# Adafruit_Pro_Trinket_3v3_modified.net
KiCad netlist of a schematic drawn in EAGLE
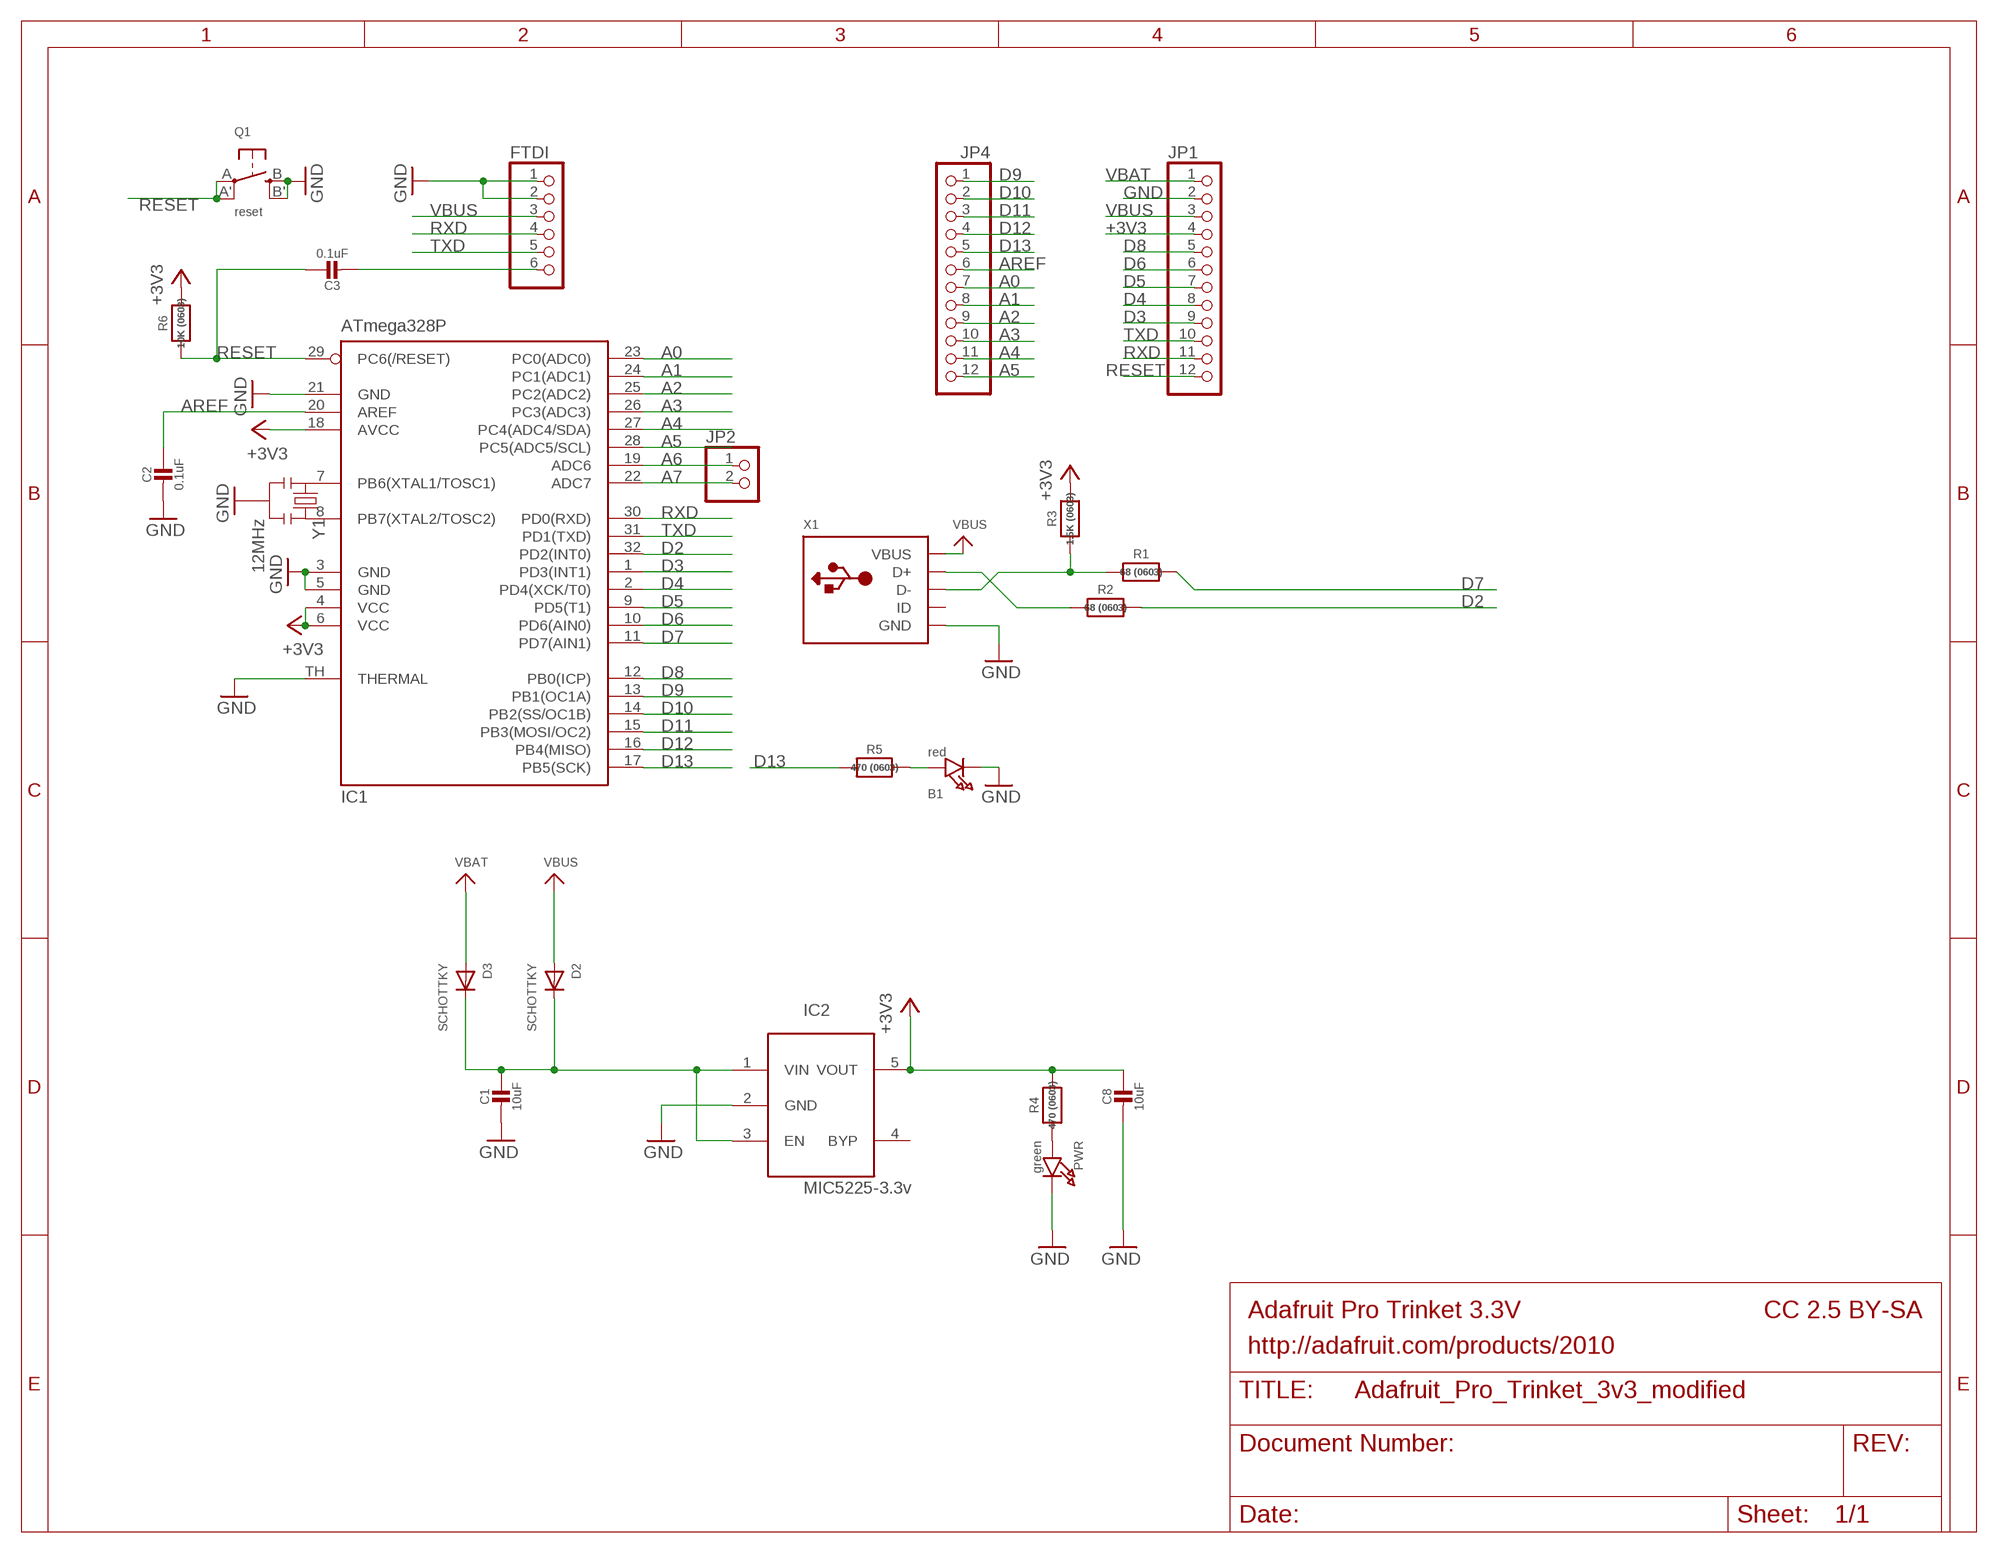
[diagram p0: schematic, sheet 1]

(export (version "E")
  (design (tool "Eeschema 10.0.6"))
  (components
    (comp (ref "B1")
      (value "red")
      (footprint "eagle-import:CHIPLED_0805_NOOUTLINE")
      (libsource (lib "eagle-import") (part "LED0805_NOOUTLINE"))
    )
    (comp (ref "C1")
      (value "10uF")
      (footprint "eagle-import:0805-NO")
      (libsource (lib "eagle-import") (part "CAP_CERAMIC0805-NOOUTLINE"))
    )
    (comp (ref "C2")
      (value "0.1uF")
      (footprint "eagle-import:_0805MP")
      (libsource (lib "eagle-import") (part "CAP_CERAMIC_0805MP"))
    )
    (comp (ref "C3")
      (value "0.1uF")
      (footprint "eagle-import:0805-NO")
      (libsource (lib "eagle-import") (part "CAP_CERAMIC0805-NOOUTLINE"))
    )
    (comp (ref "C8")
      (value "10uF")
      (footprint "eagle-import:0805-NO")
      (libsource (lib "eagle-import") (part "CAP_CERAMIC0805-NOOUTLINE"))
    )
    (comp (ref "D2")
      (value "SCHOTTKY")
      (footprint "eagle-import:ADAFRUIT_SOD-123FL")
      (libsource (lib "eagle-import") (part "ADAFRUIT_DIODE_SOD-123FL"))
    )
    (comp (ref "D3")
      (value "SCHOTTKY")
      (footprint "eagle-import:ADAFRUIT_SOD-123FL")
      (libsource (lib "eagle-import") (part "ADAFRUIT_DIODE_SOD-123FL"))
    )
    (comp (ref "FTDI")
      (value "PINHD-1X6CB")
      (footprint "eagle-import:1X06-CLEANBIG")
      (libsource (lib "eagle-import") (part "PINHD-1X6CB"))
    )
    (comp (ref "IC1")
      (value "ATmega328P")
      (footprint "eagle-import:MLF32-TH")
      (fields (field (name "MPN") "ATMEGA88PA-MU"))
      (libsource (lib "eagle-import") (part "MEGA8-MI"))
    )
    (comp (ref "IC2")
      (value "MIC5225-3.3v")
      (footprint "eagle-import:SOT23-5L")
      (libsource (lib "eagle-import") (part "LP298XS"))
    )
    (comp (ref "JP1")
      (value "PINHD-1X12-CB")
      (footprint "eagle-import:1X12-CB")
      (libsource (lib "eagle-import") (part "PINHD-1X12-CB"))
    )
    (comp (ref "JP2")
      (value "HEADER-1X2ROUND")
      (footprint "eagle-import:1X02_ROUND")
      (libsource (lib "eagle-import") (part "HEADER-1X2ROUND"))
    )
    (comp (ref "JP4")
      (value "PINHD-1X12-CB")
      (footprint "eagle-import:1X12-CB")
      (libsource (lib "eagle-import") (part "PINHD-1X12-CB"))
    )
    (comp (ref "PWR")
      (value "green")
      (footprint "eagle-import:CHIPLED_0805_NOOUTLINE")
      (libsource (lib "eagle-import") (part "LED0805_NOOUTLINE"))
    )
    (comp (ref "Q1")
      (value "reset")
      (footprint "eagle-import:BTN_KMR2_4.6X2.8")
      (libsource (lib "eagle-import") (part "SWITCH_TACT_SMT4.6X2.8"))
    )
    (comp (ref "R1")
      (value "68 (0603)")
      (footprint "eagle-import:0603-NO")
      (libsource (lib "eagle-import") (part "RESISTOR_0603_NOOUT"))
    )
    (comp (ref "R2")
      (value "68 (0603)")
      (footprint "eagle-import:0603-NO")
      (libsource (lib "eagle-import") (part "RESISTOR_0603_NOOUT"))
    )
    (comp (ref "R3")
      (value "1.5K (0603)")
      (footprint "eagle-import:0603-NO")
      (libsource (lib "eagle-import") (part "RESISTOR_0603_NOOUT"))
    )
    (comp (ref "R4")
      (value "470 (0603)")
      (footprint "eagle-import:0603-NO")
      (libsource (lib "eagle-import") (part "RESISTOR_0603_NOOUT"))
    )
    (comp (ref "R5")
      (value "470 (0603)")
      (footprint "eagle-import:0603-NO")
      (libsource (lib "eagle-import") (part "RESISTOR_0603_NOOUT"))
    )
    (comp (ref "R6")
      (value "10K (0603)")
      (footprint "eagle-import:0805-NO")
      (libsource (lib "eagle-import") (part "RESISTOR0805_NOOUTLINE"))
    )
    (comp (ref "X1")
      (value "MICROBUILDER_USBMICRO_20329")
      (footprint "eagle-import:MICROBUILDER_4UCONN_20329")
      (libsource (lib "eagle-import") (part "MICROBUILDER_USBMICRO_20329"))
    )
    (comp (ref "Y1")
      (value "12MHz")
      (footprint "eagle-import:RESONATOR-SMD")
      (libsource (lib "eagle-import") (part "RESONATORSMD"))
    )
  )
  (nets
    (net (code "1") (name "+3V3") (class "Default")
      (node (ref "C8") (pin "1") (pinfunction "1_1") (pintype "passive"))
      (node (ref "IC1") (pin "18") (pinfunction "AVCC_18") (pintype "power_in"))
      (node (ref "IC1") (pin "4") (pinfunction "VCC_4") (pintype "power_in"))
      (node (ref "IC1") (pin "6") (pinfunction "VCC_6") (pintype "power_in"))
      (node (ref "IC2") (pin "5") (pinfunction "VOUT_5") (pintype "bidirectional"))
      (node (ref "JP1") (pin "4") (pinfunction "4_4") (pintype "passive"))
      (node (ref "R3") (pin "2") (pinfunction "2_2") (pintype "passive"))
      (node (ref "R4") (pin "2") (pinfunction "2_2") (pintype "passive"))
      (node (ref "R6") (pin "2") (pinfunction "2_2") (pintype "passive"))
    )
    (net (code "2") (name "/A0") (class "Default")
      (node (ref "IC1") (pin "23") (pinfunction "PC0(ADC0)_23") (pintype "bidirectional"))
      (node (ref "JP4") (pin "7") (pinfunction "7_7") (pintype "passive"))
    )
    (net (code "3") (name "/A1") (class "Default")
      (node (ref "IC1") (pin "24") (pinfunction "PC1(ADC1)_24") (pintype "bidirectional"))
      (node (ref "JP4") (pin "8") (pinfunction "8_8") (pintype "passive"))
    )
    (net (code "4") (name "/A2") (class "Default")
      (node (ref "IC1") (pin "25") (pinfunction "PC2(ADC2)_25") (pintype "bidirectional"))
      (node (ref "JP4") (pin "9") (pinfunction "9_9") (pintype "passive"))
    )
    (net (code "5") (name "/A3") (class "Default")
      (node (ref "IC1") (pin "26") (pinfunction "PC3(ADC3)_26") (pintype "bidirectional"))
      (node (ref "JP4") (pin "10") (pinfunction "10_10") (pintype "passive"))
    )
    (net (code "6") (name "/A4") (class "Default")
      (node (ref "IC1") (pin "27") (pinfunction "PC4(ADC4/SDA)_27") (pintype "bidirectional"))
      (node (ref "JP4") (pin "11") (pinfunction "11_11") (pintype "passive"))
    )
    (net (code "7") (name "/A5") (class "Default")
      (node (ref "IC1") (pin "28") (pinfunction "PC5(ADC5/SCL)_28") (pintype "bidirectional"))
      (node (ref "JP4") (pin "12") (pinfunction "12_12") (pintype "passive"))
    )
    (net (code "8") (name "/A6") (class "Default")
      (node (ref "IC1") (pin "19") (pinfunction "ADC6_19") (pintype "bidirectional"))
      (node (ref "JP2") (pin "1") (pinfunction "1_1") (pintype "passive"))
    )
    (net (code "9") (name "/A7") (class "Default")
      (node (ref "IC1") (pin "22") (pinfunction "ADC7_22") (pintype "bidirectional"))
      (node (ref "JP2") (pin "2") (pinfunction "2_2") (pintype "passive"))
    )
    (net (code "10") (name "/AREF") (class "Default")
      (node (ref "C2") (pin "1") (pinfunction "1_1") (pintype "passive"))
      (node (ref "IC1") (pin "20") (pinfunction "AREF_20") (pintype "passive"))
      (node (ref "JP4") (pin "6") (pinfunction "6_6") (pintype "passive"))
    )
    (net (code "11") (name "/D2") (class "Default")
      (node (ref "IC1") (pin "32") (pinfunction "PD2(INT0)_32") (pintype "bidirectional"))
      (node (ref "R2") (pin "2") (pinfunction "2_2") (pintype "passive"))
    )
    (net (code "12") (name "/D3") (class "Default")
      (node (ref "IC1") (pin "1") (pinfunction "PD3(INT1)_1") (pintype "bidirectional"))
      (node (ref "JP1") (pin "9") (pinfunction "9_9") (pintype "passive"))
    )
    (net (code "13") (name "/D4") (class "Default")
      (node (ref "IC1") (pin "2") (pinfunction "PD4(XCK/T0)_2") (pintype "bidirectional"))
      (node (ref "JP1") (pin "8") (pinfunction "8_8") (pintype "passive"))
    )
    (net (code "14") (name "/D5") (class "Default")
      (node (ref "IC1") (pin "9") (pinfunction "PD5(T1)_9") (pintype "bidirectional"))
      (node (ref "JP1") (pin "7") (pinfunction "7_7") (pintype "passive"))
    )
    (net (code "15") (name "/D6") (class "Default")
      (node (ref "IC1") (pin "10") (pinfunction "PD6(AIN0)_10") (pintype "bidirectional"))
      (node (ref "JP1") (pin "6") (pinfunction "6_6") (pintype "passive"))
    )
    (net (code "16") (name "/D7") (class "Default")
      (node (ref "IC1") (pin "11") (pinfunction "PD7(AIN1)_11") (pintype "bidirectional"))
      (node (ref "R1") (pin "2") (pinfunction "2_2") (pintype "passive"))
    )
    (net (code "17") (name "/D8") (class "Default")
      (node (ref "IC1") (pin "12") (pinfunction "PB0(ICP)_12") (pintype "bidirectional"))
      (node (ref "JP1") (pin "5") (pinfunction "5_5") (pintype "passive"))
    )
    (net (code "18") (name "/D9") (class "Default")
      (node (ref "IC1") (pin "13") (pinfunction "PB1(OC1A)_13") (pintype "bidirectional"))
      (node (ref "JP4") (pin "1") (pinfunction "1_1") (pintype "passive"))
    )
    (net (code "19") (name "/D10") (class "Default")
      (node (ref "IC1") (pin "14") (pinfunction "PB2(SS/OC1B)_14") (pintype "bidirectional"))
      (node (ref "JP4") (pin "2") (pinfunction "2_2") (pintype "passive"))
    )
    (net (code "20") (name "/D11") (class "Default")
      (node (ref "IC1") (pin "15") (pinfunction "PB3(MOSI/OC2)_15") (pintype "bidirectional"))
      (node (ref "JP4") (pin "3") (pinfunction "3_3") (pintype "passive"))
    )
    (net (code "21") (name "/D12") (class "Default")
      (node (ref "IC1") (pin "16") (pinfunction "PB4(MISO)_16") (pintype "bidirectional"))
      (node (ref "JP4") (pin "4") (pinfunction "4_4") (pintype "passive"))
    )
    (net (code "22") (name "/D13") (class "Default")
      (node (ref "IC1") (pin "17") (pinfunction "PB5(SCK)_17") (pintype "bidirectional"))
      (node (ref "JP4") (pin "5") (pinfunction "5_5") (pintype "passive"))
      (node (ref "R5") (pin "2") (pinfunction "2_2") (pintype "passive"))
    )
    (net (code "23") (name "/RESET") (class "Default")
      (node (ref "C3") (pin "1") (pinfunction "1_1") (pintype "passive"))
      (node (ref "IC1") (pin "29") (pinfunction "PC6(/RESET)_29") (pintype "bidirectional"))
      (node (ref "JP1") (pin "12") (pinfunction "12_12") (pintype "passive"))
      (node (ref "Q1") (pin "A") (pinfunction "P_A") (pintype "passive"))
      (node (ref "Q1") (pin "A'") (pinfunction "P1_A'") (pintype "passive"))
      (node (ref "R6") (pin "1") (pinfunction "1_1") (pintype "passive"))
    )
    (net (code "24") (name "/RXD") (class "Default")
      (node (ref "FTDI") (pin "4") (pinfunction "4_4") (pintype "passive"))
      (node (ref "IC1") (pin "30") (pinfunction "PD0(RXD)_30") (pintype "bidirectional"))
      (node (ref "JP1") (pin "11") (pinfunction "11_11") (pintype "passive"))
    )
    (net (code "25") (name "/TXD") (class "Default")
      (node (ref "FTDI") (pin "5") (pinfunction "5_5") (pintype "passive"))
      (node (ref "IC1") (pin "31") (pinfunction "PD1(TXD)_31") (pintype "bidirectional"))
      (node (ref "JP1") (pin "10") (pinfunction "10_10") (pintype "passive"))
    )
    (net (code "26") (name "GND") (class "Default")
      (node (ref "B1") (pin "C") (pinfunction "C_C") (pintype "passive"))
      (node (ref "C1") (pin "2") (pinfunction "2_2") (pintype "passive"))
      (node (ref "C2") (pin "2") (pinfunction "2_2") (pintype "passive"))
      (node (ref "C8") (pin "2") (pinfunction "2_2") (pintype "passive"))
      (node (ref "FTDI") (pin "1") (pinfunction "1_1") (pintype "passive"))
      (node (ref "FTDI") (pin "2") (pinfunction "2_2") (pintype "passive"))
      (node (ref "IC1") (pin "21") (pinfunction "GND_21") (pintype "power_in"))
      (node (ref "IC1") (pin "3") (pinfunction "GND_3") (pintype "power_in"))
      (node (ref "IC1") (pin "5") (pinfunction "GND_5") (pintype "power_in"))
      (node (ref "IC1") (pin "TH") (pinfunction "THERMAL_TH") (pintype "passive"))
      (node (ref "IC2") (pin "2") (pinfunction "GND_2") (pintype "bidirectional"))
      (node (ref "JP1") (pin "2") (pinfunction "2_2") (pintype "passive"))
      (node (ref "PWR") (pin "C") (pinfunction "C_C") (pintype "passive"))
      (node (ref "Q1") (pin "B") (pinfunction "S_B") (pintype "passive"))
      (node (ref "Q1") (pin "B'") (pinfunction "S1_B'") (pintype "passive"))
      (node (ref "X1") (pin "BASE@1") (pinfunction "GND_BASE@1") (pintype "power_in"))
      (node (ref "X1") (pin "BASE@2") (pinfunction "GND_BASE@2") (pintype "power_in"))
      (node (ref "X1") (pin "GND") (pinfunction "GND_GND") (pintype "power_in"))
      (node (ref "X1") (pin "SPRT@1") (pinfunction "GND_SPRT@1") (pintype "power_in"))
      (node (ref "X1") (pin "SPRT@2") (pinfunction "GND_SPRT@2") (pintype "power_in"))
      (node (ref "X1") (pin "SPRT@3") (pinfunction "GND_SPRT@3") (pintype "power_in"))
      (node (ref "X1") (pin "SPRT@4") (pinfunction "GND_SPRT@4") (pintype "power_in"))
      (node (ref "Y1") (pin "2") (pinfunction "2_2") (pintype "passive"))
    )
    (net (code "27") (name "Net-(B1-PadA)") (class "Default")
      (node (ref "B1") (pin "A") (pinfunction "A_A") (pintype "passive"))
      (node (ref "R5") (pin "1") (pinfunction "1_1") (pintype "passive"))
    )
    (net (code "28") (name "Net-(C3-Pad2)") (class "Default")
      (node (ref "C3") (pin "2") (pinfunction "2_2") (pintype "passive"))
      (node (ref "FTDI") (pin "6") (pinfunction "6_6") (pintype "passive"))
    )
    (net (code "29") (name "Net-(IC1-PB6(XTAL1{slash}TOSC1))") (class "Default")
      (node (ref "IC1") (pin "7") (pinfunction "PB6(XTAL1/TOSC1)_7") (pintype "bidirectional"))
      (node (ref "Y1") (pin "1") (pinfunction "1_1") (pintype "passive"))
    )
    (net (code "30") (name "Net-(IC1-PB7(XTAL2{slash}TOSC2))") (class "Default")
      (node (ref "IC1") (pin "8") (pinfunction "PB7(XTAL2/TOSC2)_8") (pintype "bidirectional"))
      (node (ref "Y1") (pin "3") (pinfunction "3_3") (pintype "passive"))
    )
    (net (code "31") (name "Net-(IC2-EN)") (class "Default")
      (node (ref "C1") (pin "1") (pinfunction "1_1") (pintype "passive"))
      (node (ref "D2") (pin "C") (pinfunction "C_C") (pintype "passive"))
      (node (ref "D3") (pin "C") (pinfunction "C_C") (pintype "passive"))
      (node (ref "IC2") (pin "1") (pinfunction "VIN_1") (pintype "bidirectional"))
      (node (ref "IC2") (pin "3") (pinfunction "EN_3") (pintype "bidirectional"))
    )
    (net (code "32") (name "Net-(PWR-PadA)") (class "Default")
      (node (ref "PWR") (pin "A") (pinfunction "A_A") (pintype "passive"))
      (node (ref "R4") (pin "1") (pinfunction "1_1") (pintype "passive"))
    )
    (net (code "33") (name "Net-(R1-Pad1)") (class "Default")
      (node (ref "R1") (pin "1") (pinfunction "1_1") (pintype "passive"))
      (node (ref "R3") (pin "1") (pinfunction "1_1") (pintype "passive"))
      (node (ref "X1") (pin "D-") (pinfunction "D-_D-") (pintype "bidirectional"))
    )
    (net (code "34") (name "Net-(R2-Pad1)") (class "Default")
      (node (ref "R2") (pin "1") (pinfunction "1_1") (pintype "passive"))
      (node (ref "X1") (pin "D+") (pinfunction "D+_D+") (pintype "bidirectional"))
    )
    (net (code "35") (name "VBAT") (class "Default")
      (node (ref "D3") (pin "A") (pinfunction "A_A") (pintype "passive"))
      (node (ref "JP1") (pin "1") (pinfunction "1_1") (pintype "passive"))
    )
    (net (code "36") (name "VBUS") (class "Default")
      (node (ref "D2") (pin "A") (pinfunction "A_A") (pintype "passive"))
      (node (ref "FTDI") (pin "3") (pinfunction "3_3") (pintype "passive"))
      (node (ref "JP1") (pin "3") (pinfunction "3_3") (pintype "passive"))
      (node (ref "X1") (pin "VBUS") (pinfunction "VBUS_VBUS") (pintype "power_in"))
    )
    (net (code "37") (name "unconnected-(IC2-BYP-Pad4)") (class "Default")
      (node (ref "IC2") (pin "4") (pinfunction "BYP_4") (pintype "bidirectional"))
    )
    (net (code "38") (name "unconnected-(X1-PadID)") (class "Default")
      (node (ref "X1") (pin "ID") (pinfunction "ID_ID") (pintype "bidirectional"))
    )
  )
)
